# ws2812_column.net
KiCad netlist of a schematic drawn in Altium Designer
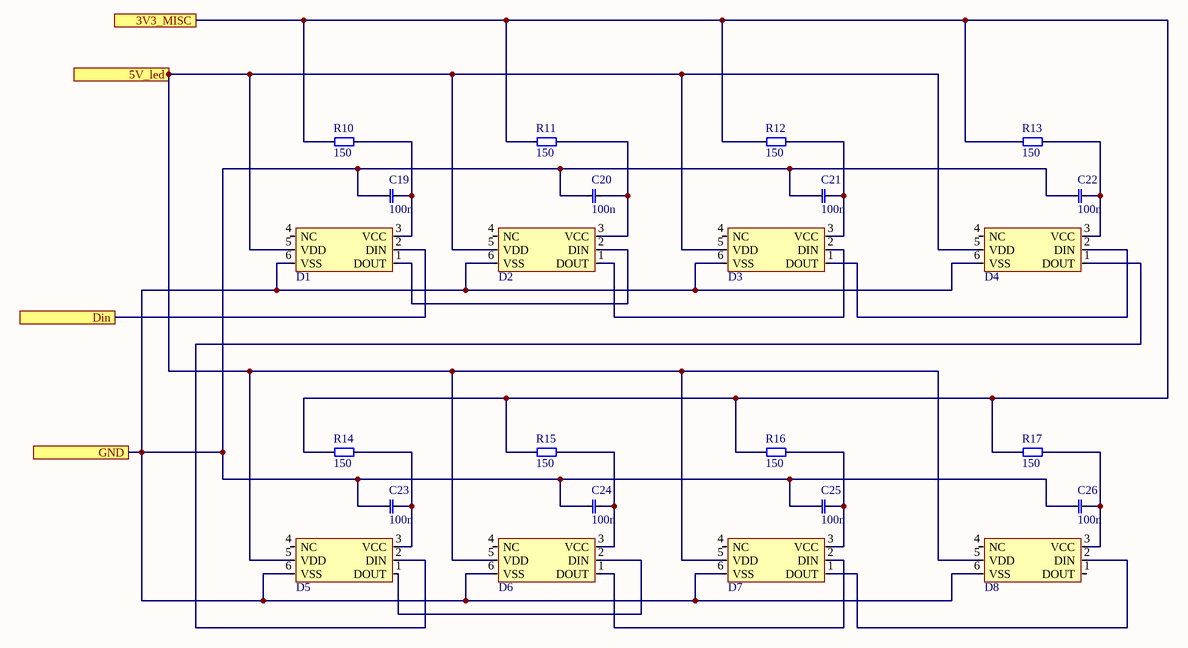
[diagram p0: ws2812_column.SchDoc]

(export (version "E")
  (design (tool "Eeschema 10.0.6"))
  (components
    (comp (ref "C19")
      (value "100n")
      (footprint "1206, capasitor")
      (fields (field (name "Comment") "1206, capacitor"))
      (libsource (lib "eitp15_lab1_lib") (part "1206, capacitor"))
    )
    (comp (ref "C20")
      (value "100n")
      (footprint "1206, capasitor")
      (fields (field (name "Comment") "1206, capacitor"))
      (libsource (lib "eitp15_lab1_lib") (part "1206, capacitor"))
    )
    (comp (ref "C21")
      (value "100n")
      (footprint "1206, capasitor")
      (fields (field (name "Comment") "1206, capacitor"))
      (libsource (lib "eitp15_lab1_lib") (part "1206, capacitor"))
    )
    (comp (ref "C22")
      (value "100n")
      (footprint "1206, capasitor")
      (fields (field (name "Comment") "1206, capacitor"))
      (libsource (lib "eitp15_lab1_lib") (part "1206, capacitor"))
    )
    (comp (ref "C23")
      (value "100n")
      (footprint "1206, capasitor")
      (fields (field (name "Comment") "1206, capacitor"))
      (libsource (lib "eitp15_lab1_lib") (part "1206, capacitor"))
    )
    (comp (ref "C24")
      (value "100n")
      (footprint "1206, capasitor")
      (fields (field (name "Comment") "1206, capacitor"))
      (libsource (lib "eitp15_lab1_lib") (part "1206, capacitor"))
    )
    (comp (ref "C25")
      (value "100n")
      (footprint "1206, capasitor")
      (fields (field (name "Comment") "1206, capacitor"))
      (libsource (lib "eitp15_lab1_lib") (part "1206, capacitor"))
    )
    (comp (ref "C26")
      (value "100n")
      (footprint "1206, capasitor")
      (fields (field (name "Comment") "1206, capacitor"))
      (libsource (lib "eitp15_lab1_lib") (part "1206, capacitor"))
    )
    (comp (ref "D1")
      (value "Neo - WS2812")
      (footprint "NEOPIXEL")
      (libsource (lib "jclib") (part "Neo - WS2812"))
    )
    (comp (ref "D2")
      (value "Neo - WS2812")
      (footprint "NEOPIXEL")
      (libsource (lib "jclib") (part "Neo - WS2812"))
    )
    (comp (ref "D3")
      (value "Neo - WS2812")
      (footprint "NEOPIXEL")
      (libsource (lib "jclib") (part "Neo - WS2812"))
    )
    (comp (ref "D4")
      (value "Neo - WS2812")
      (footprint "NEOPIXEL")
      (libsource (lib "jclib") (part "Neo - WS2812"))
    )
    (comp (ref "D5")
      (value "Neo - WS2812")
      (footprint "NEOPIXEL")
      (libsource (lib "jclib") (part "Neo - WS2812"))
    )
    (comp (ref "D6")
      (value "Neo - WS2812")
      (footprint "NEOPIXEL")
      (libsource (lib "jclib") (part "Neo - WS2812"))
    )
    (comp (ref "D7")
      (value "Neo - WS2812")
      (footprint "NEOPIXEL")
      (libsource (lib "jclib") (part "Neo - WS2812"))
    )
    (comp (ref "D8")
      (value "Neo - WS2812")
      (footprint "NEOPIXEL")
      (libsource (lib "jclib") (part "Neo - WS2812"))
    )
    (comp (ref "R10")
      (value "150")
      (footprint "1206")
      (description "Resistor")
      (fields (field (name "Comment") "1206, resistor"))
      (libsource (lib "eitp15_lab1_lib") (part "1206, resistor"))
    )
    (comp (ref "R11")
      (value "150")
      (footprint "1206")
      (description "Resistor")
      (fields (field (name "Comment") "1206, resistor"))
      (libsource (lib "eitp15_lab1_lib") (part "1206, resistor"))
    )
    (comp (ref "R12")
      (value "150")
      (footprint "1206")
      (description "Resistor")
      (fields (field (name "Comment") "1206, resistor"))
      (libsource (lib "eitp15_lab1_lib") (part "1206, resistor"))
    )
    (comp (ref "R13")
      (value "150")
      (footprint "1206")
      (description "Resistor")
      (fields (field (name "Comment") "1206, resistor"))
      (libsource (lib "eitp15_lab1_lib") (part "1206, resistor"))
    )
    (comp (ref "R14")
      (value "150")
      (footprint "1206")
      (description "Resistor")
      (fields (field (name "Comment") "1206, resistor"))
      (libsource (lib "eitp15_lab1_lib") (part "1206, resistor"))
    )
    (comp (ref "R15")
      (value "150")
      (footprint "1206")
      (description "Resistor")
      (fields (field (name "Comment") "1206, resistor"))
      (libsource (lib "eitp15_lab1_lib") (part "1206, resistor"))
    )
    (comp (ref "R16")
      (value "150")
      (footprint "1206")
      (description "Resistor")
      (fields (field (name "Comment") "1206, resistor"))
      (libsource (lib "eitp15_lab1_lib") (part "1206, resistor"))
    )
    (comp (ref "R17")
      (value "150")
      (footprint "1206")
      (description "Resistor")
      (fields (field (name "Comment") "1206, resistor"))
      (libsource (lib "eitp15_lab1_lib") (part "1206, resistor"))
    )
  )
  (nets
    (net (code "1") (name "/3V3_MISC") (class "Default")
      (node (ref "R10") (pin "1") (pinfunction "1_1") (pintype "passive"))
      (node (ref "R11") (pin "1") (pinfunction "1_1") (pintype "passive"))
      (node (ref "R12") (pin "1") (pinfunction "1_1") (pintype "passive"))
      (node (ref "R13") (pin "1") (pinfunction "1_1") (pintype "passive"))
      (node (ref "R14") (pin "1") (pinfunction "1_1") (pintype "passive"))
      (node (ref "R15") (pin "1") (pinfunction "1_1") (pintype "passive"))
      (node (ref "R16") (pin "1") (pinfunction "1_1") (pintype "passive"))
      (node (ref "R17") (pin "1") (pinfunction "1_1") (pintype "passive"))
    )
    (net (code "2") (name "/5V_led") (class "Default")
      (node (ref "D1") (pin "5") (pinfunction "VDD_5") (pintype "passive"))
      (node (ref "D2") (pin "5") (pinfunction "VDD_5") (pintype "passive"))
      (node (ref "D3") (pin "5") (pinfunction "VDD_5") (pintype "passive"))
      (node (ref "D4") (pin "5") (pinfunction "VDD_5") (pintype "passive"))
      (node (ref "D5") (pin "5") (pinfunction "VDD_5") (pintype "passive"))
      (node (ref "D6") (pin "5") (pinfunction "VDD_5") (pintype "passive"))
      (node (ref "D7") (pin "5") (pinfunction "VDD_5") (pintype "passive"))
      (node (ref "D8") (pin "5") (pinfunction "VDD_5") (pintype "passive"))
    )
    (net (code "3") (name "/Din") (class "Default")
      (node (ref "D1") (pin "2") (pinfunction "DIN_2") (pintype "passive"))
    )
    (net (code "4") (name "/GND") (class "Default")
      (node (ref "C19") (pin "0") (pinfunction "0_0") (pintype "passive"))
      (node (ref "C20") (pin "0") (pinfunction "0_0") (pintype "passive"))
      (node (ref "C21") (pin "0") (pinfunction "0_0") (pintype "passive"))
      (node (ref "C22") (pin "0") (pinfunction "0_0") (pintype "passive"))
      (node (ref "C23") (pin "0") (pinfunction "0_0") (pintype "passive"))
      (node (ref "C24") (pin "0") (pinfunction "0_0") (pintype "passive"))
      (node (ref "C25") (pin "0") (pinfunction "0_0") (pintype "passive"))
      (node (ref "C26") (pin "0") (pinfunction "0_0") (pintype "passive"))
      (node (ref "D1") (pin "6") (pinfunction "VSS_6") (pintype "passive"))
      (node (ref "D2") (pin "6") (pinfunction "VSS_6") (pintype "passive"))
      (node (ref "D3") (pin "6") (pinfunction "VSS_6") (pintype "passive"))
      (node (ref "D4") (pin "6") (pinfunction "VSS_6") (pintype "passive"))
      (node (ref "D5") (pin "6") (pinfunction "VSS_6") (pintype "passive"))
      (node (ref "D6") (pin "6") (pinfunction "VSS_6") (pintype "passive"))
      (node (ref "D7") (pin "6") (pinfunction "VSS_6") (pintype "passive"))
      (node (ref "D8") (pin "6") (pinfunction "VSS_6") (pintype "passive"))
    )
    (net (code "5") (name "Net-(D1-DOUT)") (class "Default")
      (node (ref "D1") (pin "1") (pinfunction "DOUT_1") (pintype "passive"))
      (node (ref "D2") (pin "2") (pinfunction "DIN_2") (pintype "passive"))
    )
    (net (code "6") (name "Net-(D1-VCC)") (class "Default")
      (node (ref "C19") (pin "1") (pinfunction "1_1") (pintype "passive"))
      (node (ref "D1") (pin "3") (pinfunction "VCC_3") (pintype "passive"))
      (node (ref "R10") (pin "0") (pinfunction "0_0") (pintype "passive"))
    )
    (net (code "7") (name "Net-(D2-DOUT)") (class "Default")
      (node (ref "D2") (pin "1") (pinfunction "DOUT_1") (pintype "passive"))
      (node (ref "D3") (pin "2") (pinfunction "DIN_2") (pintype "passive"))
    )
    (net (code "8") (name "Net-(D2-VCC)") (class "Default")
      (node (ref "C20") (pin "1") (pinfunction "1_1") (pintype "passive"))
      (node (ref "D2") (pin "3") (pinfunction "VCC_3") (pintype "passive"))
      (node (ref "R11") (pin "0") (pinfunction "0_0") (pintype "passive"))
    )
    (net (code "9") (name "Net-(D3-DOUT)") (class "Default")
      (node (ref "D3") (pin "1") (pinfunction "DOUT_1") (pintype "passive"))
      (node (ref "D4") (pin "2") (pinfunction "DIN_2") (pintype "passive"))
    )
    (net (code "10") (name "Net-(D3-VCC)") (class "Default")
      (node (ref "C21") (pin "1") (pinfunction "1_1") (pintype "passive"))
      (node (ref "D3") (pin "3") (pinfunction "VCC_3") (pintype "passive"))
      (node (ref "R12") (pin "0") (pinfunction "0_0") (pintype "passive"))
    )
    (net (code "11") (name "Net-(D4-DOUT)") (class "Default")
      (node (ref "D4") (pin "1") (pinfunction "DOUT_1") (pintype "passive"))
      (node (ref "D5") (pin "2") (pinfunction "DIN_2") (pintype "passive"))
    )
    (net (code "12") (name "Net-(D4-VCC)") (class "Default")
      (node (ref "C22") (pin "1") (pinfunction "1_1") (pintype "passive"))
      (node (ref "D4") (pin "3") (pinfunction "VCC_3") (pintype "passive"))
      (node (ref "R13") (pin "0") (pinfunction "0_0") (pintype "passive"))
    )
    (net (code "13") (name "Net-(D5-DOUT)") (class "Default")
      (node (ref "D5") (pin "1") (pinfunction "DOUT_1") (pintype "passive"))
      (node (ref "D6") (pin "2") (pinfunction "DIN_2") (pintype "passive"))
    )
    (net (code "14") (name "Net-(D5-VCC)") (class "Default")
      (node (ref "C23") (pin "1") (pinfunction "1_1") (pintype "passive"))
      (node (ref "D5") (pin "3") (pinfunction "VCC_3") (pintype "passive"))
      (node (ref "R14") (pin "0") (pinfunction "0_0") (pintype "passive"))
    )
    (net (code "15") (name "Net-(D6-DOUT)") (class "Default")
      (node (ref "D6") (pin "1") (pinfunction "DOUT_1") (pintype "passive"))
      (node (ref "D7") (pin "2") (pinfunction "DIN_2") (pintype "passive"))
    )
    (net (code "16") (name "Net-(D6-VCC)") (class "Default")
      (node (ref "C24") (pin "1") (pinfunction "1_1") (pintype "passive"))
      (node (ref "D6") (pin "3") (pinfunction "VCC_3") (pintype "passive"))
      (node (ref "R15") (pin "0") (pinfunction "0_0") (pintype "passive"))
    )
    (net (code "17") (name "Net-(D7-DOUT)") (class "Default")
      (node (ref "D7") (pin "1") (pinfunction "DOUT_1") (pintype "passive"))
      (node (ref "D8") (pin "2") (pinfunction "DIN_2") (pintype "passive"))
    )
    (net (code "18") (name "Net-(D7-VCC)") (class "Default")
      (node (ref "C25") (pin "1") (pinfunction "1_1") (pintype "passive"))
      (node (ref "D7") (pin "3") (pinfunction "VCC_3") (pintype "passive"))
      (node (ref "R16") (pin "0") (pinfunction "0_0") (pintype "passive"))
    )
    (net (code "19") (name "Net-(D8-VCC)") (class "Default")
      (node (ref "C26") (pin "1") (pinfunction "1_1") (pintype "passive"))
      (node (ref "D8") (pin "3") (pinfunction "VCC_3") (pintype "passive"))
      (node (ref "R17") (pin "0") (pinfunction "0_0") (pintype "passive"))
    )
    (net (code "20") (name "unconnected-(D1-NC-Pad4)") (class "Default")
      (node (ref "D1") (pin "4") (pinfunction "NC_4") (pintype "passive"))
    )
    (net (code "21") (name "unconnected-(D2-NC-Pad4)") (class "Default")
      (node (ref "D2") (pin "4") (pinfunction "NC_4") (pintype "passive"))
    )
    (net (code "22") (name "unconnected-(D3-NC-Pad4)") (class "Default")
      (node (ref "D3") (pin "4") (pinfunction "NC_4") (pintype "passive"))
    )
    (net (code "23") (name "unconnected-(D4-NC-Pad4)") (class "Default")
      (node (ref "D4") (pin "4") (pinfunction "NC_4") (pintype "passive"))
    )
    (net (code "24") (name "unconnected-(D5-NC-Pad4)") (class "Default")
      (node (ref "D5") (pin "4") (pinfunction "NC_4") (pintype "passive"))
    )
    (net (code "25") (name "unconnected-(D6-NC-Pad4)") (class "Default")
      (node (ref "D6") (pin "4") (pinfunction "NC_4") (pintype "passive"))
    )
    (net (code "26") (name "unconnected-(D7-NC-Pad4)") (class "Default")
      (node (ref "D7") (pin "4") (pinfunction "NC_4") (pintype "passive"))
    )
    (net (code "27") (name "unconnected-(D8-DOUT-Pad1)") (class "Default")
      (node (ref "D8") (pin "1") (pinfunction "DOUT_1") (pintype "passive"))
    )
    (net (code "28") (name "unconnected-(D8-NC-Pad4)") (class "Default")
      (node (ref "D8") (pin "4") (pinfunction "NC_4") (pintype "passive"))
    )
  )
)
